# Peripherals.net
KiCad netlist of a schematic drawn in Altium Designer
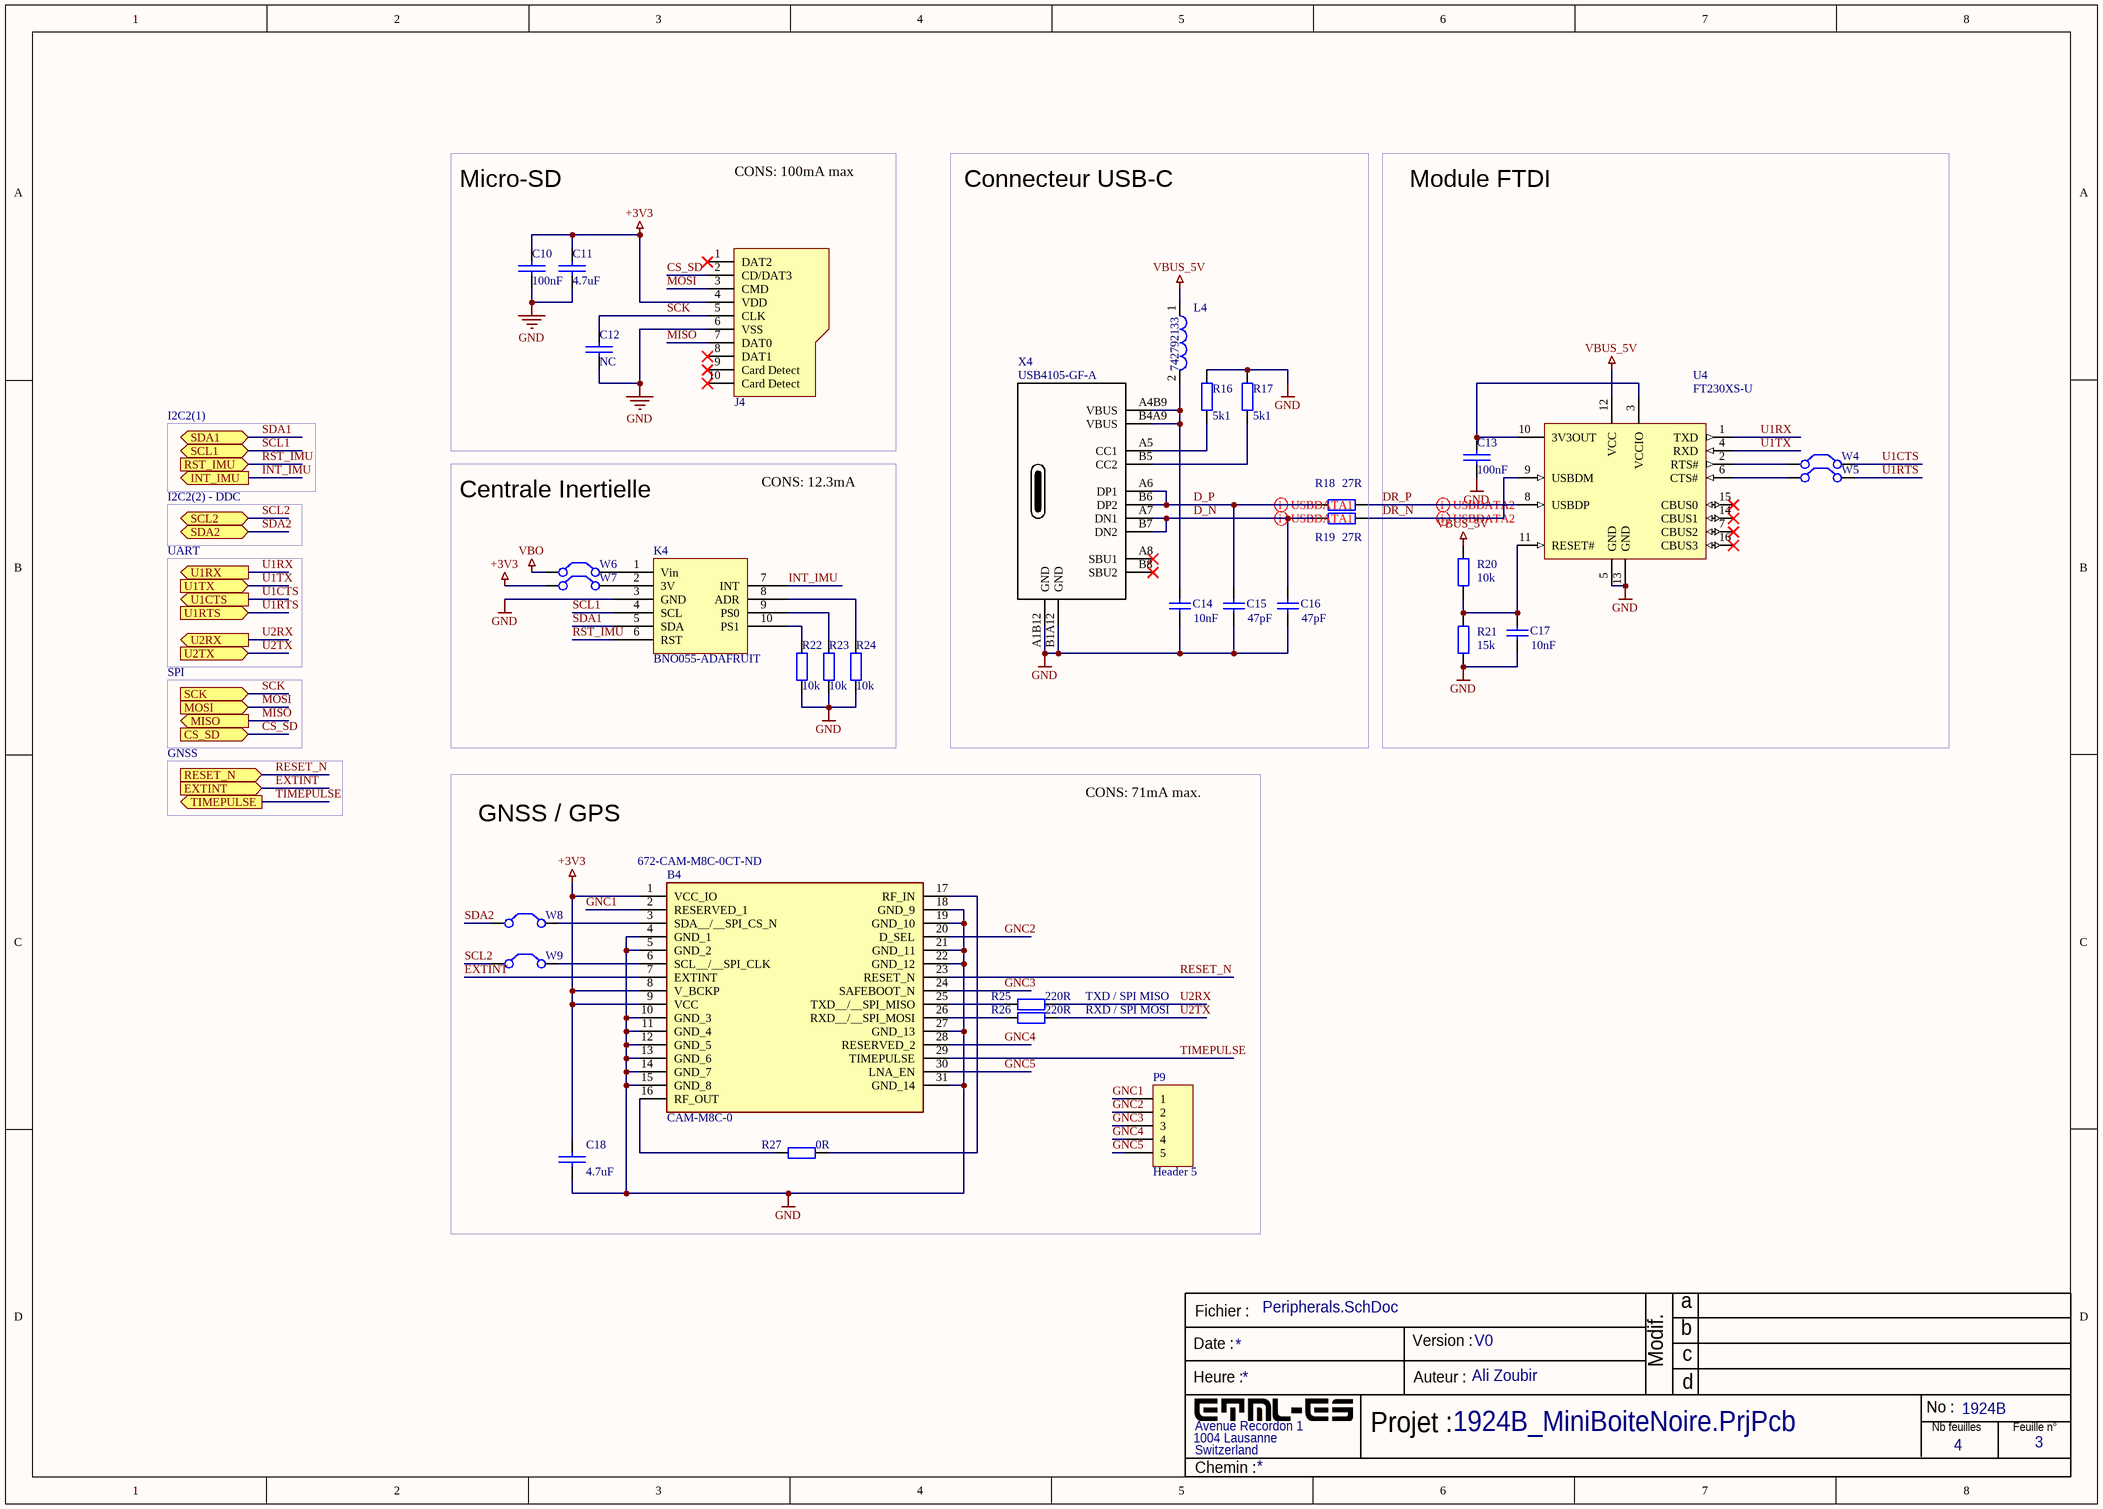
[diagram p0: Peripherals.SchDoc]

(export (version "E")
  (design (tool "Eeschema 10.0.6"))
  (components
    (comp (ref "B4")
      (value "CAM-M8C-0")
      (footprint "CAMM8C0")
      (description "RF RCVR GNSS/GPS 1.575GHZ MODULE")
      (fields
        (field (name "MOUSER PART NUMBER") "377-CAM-M8C-0")
        (field (name "SUPPLIER PART NUMBER 1") "672-CAM-M8C-0CT-ND")
      )
      (libsource (lib "CAM-M8C-0") (part "CAM-M8C-0"))
    )
    (comp (ref "C10") (value "100nF") (footprint "Cap_0805") (libsource (lib "*") (part "C")))
    (comp (ref "C11") (value "4.7uF") (footprint "Cap_0805") (libsource (lib "*") (part "C")))
    (comp (ref "C12") (value "NC") (footprint "Cap_0805") (libsource (lib "*") (part "C")))
    (comp (ref "C13") (value "100nF") (footprint "Cap_0805") (libsource (lib "*") (part "C")))
    (comp (ref "C14")
      (value "10nF")
      (footprint "6-0805_L")
      (description "Capacitor")
      (fields (field (name "PUBLISHER") "Altium Limited"))
      (libsource (lib "Miscellaneous Devices") (part "Cap"))
    )
    (comp (ref "C15")
      (value "47pF")
      (footprint "6-0805_L")
      (description "Capacitor")
      (fields (field (name "PUBLISHER") "Altium Limited"))
      (libsource (lib "Miscellaneous Devices") (part "Cap"))
    )
    (comp (ref "C16")
      (value "47pF")
      (footprint "6-0805_L")
      (description "Capacitor")
      (fields (field (name "PUBLISHER") "Altium Limited"))
      (libsource (lib "Miscellaneous Devices") (part "Cap"))
    )
    (comp (ref "C17")
      (value "10nF")
      (footprint "Cap_0805")
      (description "Capacitor")
      (fields (field (name "PUBLISHER") "Altium Limited"))
      (libsource (lib "Miscellaneous Devices") (part "Cap"))
    )
    (comp (ref "C18") (value "4.7uF") (footprint "Cap_0805") (libsource (lib "*") (part "C")))
    (comp (ref "J4")
      (value "693071010811")
      (footprint "uSD-WE-693071010811")
      (description "WR-CRD Micro SD Card Connector Push & Push")
      (fields (field (name "MANUFACTURER") "Wurth Elektronik"))
      (libsource (lib "AZR-LIB") (part "uSD-WE-693071010811"))
    )
    (comp (ref "K4")
      (value "BNO055-ADAFRUIT")
      (footprint "BNO055-ADAFRUIT_NO_HOLES")
      (libsource (lib "2221-LIB") (part "BNO055-ADAFRUIT"))
    )
    (comp (ref "L4")
      (value "742792133")
      (footprint "SMD-1206")
      (description "SMD EMI Suppression Ferrite Bead WE-CBF, Z = 600 Ohm")
      (libsource (lib "Altium Content Vault") (part "PAS-IND-INDUCTOR-2"))
    )
    (comp (ref "P9")
      (value "Header 5")
      (footprint "HDR1X5")
      (description "Header, 5-Pin")
      (fields (field (name "PUBLISHER") "Altium Limited"))
      (libsource (lib "Miscellaneous Connectors") (part "Header 5"))
    )
    (comp (ref "R16")
      (value "5k1")
      (footprint "RES_0805")
      (description "Res 0805")
      (fields (field (name "PUBLISHER") "Altium Limited"))
      (libsource (lib "Miscellaneous Devices") (part "Res2"))
    )
    (comp (ref "R17")
      (value "5k1")
      (footprint "RES_0805")
      (description "Res 0805")
      (fields (field (name "PUBLISHER") "Altium Limited"))
      (libsource (lib "Miscellaneous Devices") (part "Res2"))
    )
    (comp (ref "R18")
      (value "27R")
      (footprint "RES_0805")
      (description "Res 0805")
      (fields (field (name "PUBLISHER") "Altium Limited"))
      (libsource (lib "") (part "Res2_2"))
    )
    (comp (ref "R19")
      (value "27R")
      (footprint "RES_0805")
      (description "Res 0805")
      (fields (field (name "PUBLISHER") "Altium Limited"))
      (libsource (lib "") (part "Res2_2"))
    )
    (comp (ref "R20")
      (value "10k")
      (footprint "RES_0805")
      (description "Res 0805")
      (fields (field (name "PUBLISHER") "Altium Limited"))
      (libsource (lib "Miscellaneous Devices") (part "Res2"))
    )
    (comp (ref "R21")
      (value "15k")
      (footprint "RES_0805")
      (description "Res 0805")
      (fields (field (name "PUBLISHER") "Altium Limited"))
      (libsource (lib "Miscellaneous Devices") (part "Res2"))
    )
    (comp (ref "R22")
      (value "10k")
      (footprint "RES_0805")
      (description "Res 0805")
      (fields (field (name "PUBLISHER") "Altium Limited"))
      (libsource (lib "Miscellaneous Devices") (part "Res2"))
    )
    (comp (ref "R23")
      (value "10k")
      (footprint "RES_0805")
      (description "Res 0805")
      (fields (field (name "PUBLISHER") "Altium Limited"))
      (libsource (lib "Miscellaneous Devices") (part "Res2"))
    )
    (comp (ref "R24")
      (value "10k")
      (footprint "RES_0805")
      (description "Res 0805")
      (fields (field (name "PUBLISHER") "Altium Limited"))
      (libsource (lib "Miscellaneous Devices") (part "Res2"))
    )
    (comp (ref "R25")
      (value "220R")
      (footprint "RES_0805")
      (description "Res 0805")
      (fields (field (name "PUBLISHER") "Altium Limited"))
      (libsource (lib "") (part "Res2_1"))
    )
    (comp (ref "R26")
      (value "220R")
      (footprint "RES_0805")
      (description "Res 0805")
      (fields (field (name "PUBLISHER") "Altium Limited"))
      (libsource (lib "") (part "Res2_1"))
    )
    (comp (ref "R27")
      (value "0R")
      (footprint "RES_0805")
      (description "Res 0805")
      (fields (field (name "Comment") "220R") (field (name "PUBLISHER") "Altium Limited"))
      (libsource (lib "") (part "Res2_1"))
    )
    (comp (ref "U4")
      (value "FT230XS-U")
      (footprint "SSOP-16_N")
      (fields (field (name "MANUFACTURER") "FTDI"))
      (libsource (lib "Altium Content Vault") (part "COM-USB-FT230XS-IL16"))
    )
    (comp (ref "W4")
      (value "Jumper")
      (footprint "JUMPER")
      (description "Jumper Wire")
      (fields (field (name "PUBLISHER") "Altium Limited"))
      (libsource (lib "Miscellaneous Devices") (part "Jumper"))
    )
    (comp (ref "W5")
      (value "Jumper")
      (footprint "JUMPER")
      (description "Jumper Wire")
      (fields (field (name "PUBLISHER") "Altium Limited"))
      (libsource (lib "Miscellaneous Devices") (part "Jumper"))
    )
    (comp (ref "W6")
      (value "Jumper")
      (footprint "JUMPER")
      (description "Jumper Wire")
      (fields (field (name "PUBLISHER") "Altium Limited"))
      (libsource (lib "Miscellaneous Devices") (part "Jumper"))
    )
    (comp (ref "W7")
      (value "Jumper")
      (footprint "JUMPER")
      (description "Jumper Wire")
      (fields (field (name "PUBLISHER") "Altium Limited"))
      (libsource (lib "Miscellaneous Devices") (part "Jumper"))
    )
    (comp (ref "W8")
      (value "Jumper")
      (footprint "JUMPER")
      (description "Jumper Wire")
      (fields (field (name "PUBLISHER") "Altium Limited"))
      (libsource (lib "Miscellaneous Devices") (part "Jumper"))
    )
    (comp (ref "W9")
      (value "Jumper")
      (footprint "JUMPER")
      (description "Jumper Wire")
      (fields (field (name "PUBLISHER") "Altium Limited"))
      (libsource (lib "Miscellaneous Devices") (part "Jumper"))
    )
    (comp (ref "X4")
      (value "USB4105-GF-A")
      (footprint "GCT_USB4105-GF-A")
      (description "USB4105-GF-A USB connector")
      (libsource (lib "2221-LIB") (part "USB-C Type 2.0"))
    )
  )
  (nets
    (net (code "1") (name "+3V3") (class "Default")
      (node (ref "B4") (pin "1") (pinfunction "VCC_IO_1") (pintype "passive"))
      (node (ref "B4") (pin "8") (pinfunction "V_BCKP_8") (pintype "passive"))
      (node (ref "B4") (pin "9") (pinfunction "VCC_9") (pintype "passive"))
      (node (ref "C10") (pin "1") (pinfunction "1_1") (pintype "passive"))
      (node (ref "C11") (pin "1") (pinfunction "1_1") (pintype "passive"))
      (node (ref "C18") (pin "1") (pinfunction "1_1") (pintype "passive"))
      (node (ref "J4") (pin "4") (pinfunction "VDD_4") (pintype "passive"))
      (node (ref "W7") (pin "1") (pinfunction "C1_1") (pintype "passive"))
    )
    (net (code "2") (name "/CS_SD") (class "Default")
      (node (ref "J4") (pin "2") (pinfunction "CD/DAT3_2") (pintype "passive"))
    )
    (net (code "3") (name "/DR_N") (class "Default")
      (node (ref "R19") (pin "2") (pinfunction "2_2") (pintype "passive"))
      (node (ref "U4") (pin "9") (pinfunction "USBDM_9") (pintype "input"))
    )
    (net (code "4") (name "/DR_P") (class "Default")
      (node (ref "R18") (pin "2") (pinfunction "2_2") (pintype "passive"))
      (node (ref "U4") (pin "8") (pinfunction "USBDP_8") (pintype "input"))
    )
    (net (code "5") (name "/D_N") (class "Default")
      (node (ref "C16") (pin "2") (pinfunction "2_2") (pintype "passive"))
      (node (ref "R19") (pin "1") (pinfunction "1_1") (pintype "passive"))
      (node (ref "X4") (pin "A7") (pinfunction "DN1_A7") (pintype "passive"))
      (node (ref "X4") (pin "B7") (pinfunction "DN2_B7") (pintype "passive"))
    )
    (net (code "6") (name "/D_P") (class "Default")
      (node (ref "C15") (pin "2") (pinfunction "2_2") (pintype "passive"))
      (node (ref "R18") (pin "1") (pinfunction "1_1") (pintype "passive"))
      (node (ref "X4") (pin "A6") (pinfunction "DP1_A6") (pintype "passive"))
      (node (ref "X4") (pin "B6") (pinfunction "DP2_B6") (pintype "passive"))
    )
    (net (code "7") (name "/EXTINT") (class "Default")
      (node (ref "B4") (pin "7") (pinfunction "EXTINT_7") (pintype "passive"))
    )
    (net (code "8") (name "/GNC1") (class "Default")
      (node (ref "B4") (pin "2") (pinfunction "RESERVED_1_2") (pintype "passive"))
      (node (ref "P9") (pin "1") (pinfunction "1_1") (pintype "passive"))
    )
    (net (code "9") (name "/GNC2") (class "Default")
      (node (ref "B4") (pin "20") (pinfunction "D_SEL_20") (pintype "passive"))
      (node (ref "P9") (pin "2") (pinfunction "2_2") (pintype "passive"))
    )
    (net (code "10") (name "/GNC3") (class "Default")
      (node (ref "B4") (pin "24") (pinfunction "SAFEBOOT_N_24") (pintype "passive"))
      (node (ref "P9") (pin "3") (pinfunction "3_3") (pintype "passive"))
    )
    (net (code "11") (name "/GNC4") (class "Default")
      (node (ref "B4") (pin "28") (pinfunction "RESERVED_2_28") (pintype "passive"))
      (node (ref "P9") (pin "4") (pinfunction "4_4") (pintype "passive"))
    )
    (net (code "12") (name "/GNC5") (class "Default")
      (node (ref "B4") (pin "30") (pinfunction "LNA_EN_30") (pintype "passive"))
      (node (ref "P9") (pin "5") (pinfunction "5_5") (pintype "passive"))
    )
    (net (code "13") (name "/INT_IMU") (class "Default")
      (node (ref "K4") (pin "7") (pinfunction "INT_7") (pintype "passive"))
    )
    (net (code "14") (name "/MISO") (class "Default")
      (node (ref "J4") (pin "7") (pinfunction "DAT0_7") (pintype "passive"))
    )
    (net (code "15") (name "/MOSI") (class "Default")
      (node (ref "J4") (pin "3") (pinfunction "CMD_3") (pintype "passive"))
    )
    (net (code "16") (name "/RESET_N") (class "Default")
      (node (ref "B4") (pin "23") (pinfunction "RESET_N_23") (pintype "passive"))
    )
    (net (code "17") (name "/RST_IMU") (class "Default")
      (node (ref "K4") (pin "6") (pinfunction "RST_6") (pintype "passive"))
    )
    (net (code "18") (name "/SCK") (class "Default")
      (node (ref "C12") (pin "1") (pinfunction "1_1") (pintype "passive"))
      (node (ref "J4") (pin "5") (pinfunction "CLK_5") (pintype "passive"))
    )
    (net (code "19") (name "/SCL1") (class "Default")
      (node (ref "K4") (pin "4") (pinfunction "SCL_4") (pintype "passive"))
    )
    (net (code "20") (name "/SCL2") (class "Default")
      (node (ref "W9") (pin "1") (pinfunction "C1_1") (pintype "passive"))
    )
    (net (code "21") (name "/SDA1") (class "Default")
      (node (ref "K4") (pin "5") (pinfunction "SDA_5") (pintype "passive"))
    )
    (net (code "22") (name "/SDA2") (class "Default")
      (node (ref "W8") (pin "1") (pinfunction "C1_1") (pintype "passive"))
    )
    (net (code "23") (name "/TIMEPULSE") (class "Default")
      (node (ref "B4") (pin "29") (pinfunction "TIMEPULSE_29") (pintype "passive"))
    )
    (net (code "24") (name "/U1CTS") (class "Default")
      (node (ref "W4") (pin "2") (pinfunction "C2_2") (pintype "passive"))
    )
    (net (code "25") (name "/U1RTS") (class "Default")
      (node (ref "W5") (pin "2") (pinfunction "C2_2") (pintype "passive"))
    )
    (net (code "26") (name "/U1RX") (class "Default")
      (node (ref "U4") (pin "1") (pinfunction "TXD_1") (pintype "output"))
    )
    (net (code "27") (name "/U1TX") (class "Default")
      (node (ref "U4") (pin "4") (pinfunction "RXD_4") (pintype "input"))
    )
    (net (code "28") (name "/U2RX") (class "Default")
      (node (ref "R25") (pin "1") (pinfunction "1_1") (pintype "passive"))
    )
    (net (code "29") (name "/U2TX") (class "Default")
      (node (ref "R26") (pin "1") (pinfunction "1_1") (pintype "passive"))
    )
    (net (code "30") (name "GND") (class "Default")
      (node (ref "B4") (pin "10") (pinfunction "GND_3_10") (pintype "passive"))
      (node (ref "B4") (pin "11") (pinfunction "GND_4_11") (pintype "passive"))
      (node (ref "B4") (pin "12") (pinfunction "GND_5_12") (pintype "passive"))
      (node (ref "B4") (pin "13") (pinfunction "GND_6_13") (pintype "passive"))
      (node (ref "B4") (pin "14") (pinfunction "GND_7_14") (pintype "passive"))
      (node (ref "B4") (pin "15") (pinfunction "GND_8_15") (pintype "passive"))
      (node (ref "B4") (pin "18") (pinfunction "GND_9_18") (pintype "passive"))
      (node (ref "B4") (pin "19") (pinfunction "GND_10_19") (pintype "passive"))
      (node (ref "B4") (pin "21") (pinfunction "GND_11_21") (pintype "passive"))
      (node (ref "B4") (pin "22") (pinfunction "GND_12_22") (pintype "passive"))
      (node (ref "B4") (pin "27") (pinfunction "GND_13_27") (pintype "passive"))
      (node (ref "B4") (pin "31") (pinfunction "GND_14_31") (pintype "passive"))
      (node (ref "B4") (pin "4") (pinfunction "GND_1_4") (pintype "passive"))
      (node (ref "B4") (pin "5") (pinfunction "GND_2_5") (pintype "passive"))
      (node (ref "C10") (pin "2") (pinfunction "2_2") (pintype "passive"))
      (node (ref "C11") (pin "2") (pinfunction "2_2") (pintype "passive"))
      (node (ref "C12") (pin "2") (pinfunction "2_2") (pintype "passive"))
      (node (ref "C13") (pin "2") (pinfunction "2_2") (pintype "passive"))
      (node (ref "C14") (pin "1") (pinfunction "1_1") (pintype "passive"))
      (node (ref "C15") (pin "1") (pinfunction "1_1") (pintype "passive"))
      (node (ref "C16") (pin "1") (pinfunction "1_1") (pintype "passive"))
      (node (ref "C17") (pin "1") (pinfunction "1_1") (pintype "passive"))
      (node (ref "C18") (pin "2") (pinfunction "2_2") (pintype "passive"))
      (node (ref "J4") (pin "6") (pinfunction "VSS_6") (pintype "passive"))
      (node (ref "K4") (pin "3") (pinfunction "GND_3") (pintype "passive"))
      (node (ref "R16") (pin "2") (pinfunction "2_2") (pintype "passive"))
      (node (ref "R17") (pin "2") (pinfunction "2_2") (pintype "passive"))
      (node (ref "R21") (pin "1") (pinfunction "1_1") (pintype "passive"))
      (node (ref "R22") (pin "1") (pinfunction "1_1") (pintype "passive"))
      (node (ref "R23") (pin "1") (pinfunction "1_1") (pintype "passive"))
      (node (ref "R24") (pin "1") (pinfunction "1_1") (pintype "passive"))
      (node (ref "U4") (pin "13") (pinfunction "GND_13") (pintype "power_in"))
      (node (ref "U4") (pin "5") (pinfunction "GND_5") (pintype "power_in"))
      (node (ref "X4") (pin "A1B12") (pinfunction "GND_A1B12") (pintype "passive"))
      (node (ref "X4") (pin "B1A12") (pinfunction "GND_B1A12") (pintype "passive"))
    )
    (net (code "31") (name "Net-(B4-RF_IN)") (class "Default")
      (node (ref "B4") (pin "17") (pinfunction "RF_IN_17") (pintype "passive"))
      (node (ref "R27") (pin "1") (pinfunction "1_1") (pintype "passive"))
    )
    (net (code "32") (name "Net-(B4-RF_OUT)") (class "Default")
      (node (ref "B4") (pin "16") (pinfunction "RF_OUT_16") (pintype "passive"))
      (node (ref "R27") (pin "2") (pinfunction "2_2") (pintype "passive"))
    )
    (net (code "33") (name "Net-(B4-RXD__{slash}__SPI_MOSI)") (class "Default")
      (node (ref "B4") (pin "26") (pinfunction "RXD__/__SPI_MOSI_26") (pintype "passive"))
      (node (ref "R26") (pin "2") (pinfunction "2_2") (pintype "passive"))
    )
    (net (code "34") (name "Net-(B4-SCL__{slash}__SPI_CLK)") (class "Default")
      (node (ref "B4") (pin "6") (pinfunction "SCL__/__SPI_CLK_6") (pintype "passive"))
      (node (ref "W9") (pin "2") (pinfunction "C2_2") (pintype "passive"))
    )
    (net (code "35") (name "Net-(B4-SDA__{slash}__SPI_CS_N)") (class "Default")
      (node (ref "B4") (pin "3") (pinfunction "SDA__/__SPI_CS_N_3") (pintype "passive"))
      (node (ref "W8") (pin "2") (pinfunction "C2_2") (pintype "passive"))
    )
    (net (code "36") (name "Net-(B4-TXD__{slash}__SPI_MISO)") (class "Default")
      (node (ref "B4") (pin "25") (pinfunction "TXD__/__SPI_MISO_25") (pintype "passive"))
      (node (ref "R25") (pin "2") (pinfunction "2_2") (pintype "passive"))
    )
    (net (code "37") (name "Net-(C14-Pad2)") (class "Default")
      (node (ref "C14") (pin "2") (pinfunction "2_2") (pintype "passive"))
      (node (ref "L4") (pin "2") (pinfunction "2_2") (pintype "passive"))
      (node (ref "X4") (pin "A4B9") (pinfunction "VBUS_A4B9") (pintype "passive"))
      (node (ref "X4") (pin "B4A9") (pinfunction "VBUS_B4A9") (pintype "passive"))
    )
    (net (code "38") (name "Net-(K4-3V)") (class "Default")
      (node (ref "K4") (pin "2") (pinfunction "3V_2") (pintype "passive"))
      (node (ref "W7") (pin "2") (pinfunction "C2_2") (pintype "passive"))
    )
    (net (code "39") (name "Net-(K4-ADR)") (class "Default")
      (node (ref "K4") (pin "8") (pinfunction "ADR_8") (pintype "passive"))
      (node (ref "R24") (pin "2") (pinfunction "2_2") (pintype "passive"))
    )
    (net (code "40") (name "Net-(K4-PS0)") (class "Default")
      (node (ref "K4") (pin "9") (pinfunction "PS0_9") (pintype "passive"))
      (node (ref "R23") (pin "2") (pinfunction "2_2") (pintype "passive"))
    )
    (net (code "41") (name "Net-(K4-PS1)") (class "Default")
      (node (ref "K4") (pin "10") (pinfunction "PS1_10") (pintype "passive"))
      (node (ref "R22") (pin "2") (pinfunction "2_2") (pintype "passive"))
    )
    (net (code "42") (name "Net-(K4-Vin)") (class "Default")
      (node (ref "K4") (pin "1") (pinfunction "Vin_1") (pintype "passive"))
      (node (ref "W6") (pin "2") (pinfunction "C2_2") (pintype "passive"))
    )
    (net (code "43") (name "Net-(U4-3V3OUT)") (class "Default")
      (node (ref "C13") (pin "1") (pinfunction "1_1") (pintype "passive"))
      (node (ref "U4") (pin "10") (pinfunction "3V3OUT_10") (pintype "power_in"))
      (node (ref "U4") (pin "3") (pinfunction "VCCIO_3") (pintype "power_in"))
    )
    (net (code "44") (name "Net-(U4-CTS#)") (class "Default")
      (node (ref "U4") (pin "6") (pinfunction "CTS#_6") (pintype "input"))
      (node (ref "W5") (pin "1") (pinfunction "C1_1") (pintype "passive"))
    )
    (net (code "45") (name "Net-(U4-RESET#)") (class "Default")
      (node (ref "C17") (pin "2") (pinfunction "2_2") (pintype "passive"))
      (node (ref "R20") (pin "1") (pinfunction "1_1") (pintype "passive"))
      (node (ref "R21") (pin "2") (pinfunction "2_2") (pintype "passive"))
      (node (ref "U4") (pin "11") (pinfunction "RESET#_11") (pintype "input"))
    )
    (net (code "46") (name "Net-(U4-RTS#)") (class "Default")
      (node (ref "U4") (pin "2") (pinfunction "RTS#_2") (pintype "output"))
      (node (ref "W4") (pin "1") (pinfunction "C1_1") (pintype "passive"))
    )
    (net (code "47") (name "Net-(X4-CC1)") (class "Default")
      (node (ref "R16") (pin "1") (pinfunction "1_1") (pintype "passive"))
      (node (ref "X4") (pin "A5") (pinfunction "CC1_A5") (pintype "passive"))
    )
    (net (code "48") (name "Net-(X4-CC2)") (class "Default")
      (node (ref "R17") (pin "1") (pinfunction "1_1") (pintype "passive"))
      (node (ref "X4") (pin "B5") (pinfunction "CC2_B5") (pintype "passive"))
    )
    (net (code "49") (name "VBO") (class "Default")
      (node (ref "W6") (pin "1") (pinfunction "C1_1") (pintype "passive"))
    )
    (net (code "50") (name "VBUS_5V") (class "Default")
      (node (ref "L4") (pin "1") (pinfunction "1_1") (pintype "passive"))
      (node (ref "R20") (pin "2") (pinfunction "2_2") (pintype "passive"))
      (node (ref "U4") (pin "12") (pinfunction "VCC_12") (pintype "power_in"))
    )
    (net (code "51") (name "unconnected-(J4-Card_Detect-Pad9)") (class "Default")
      (node (ref "J4") (pin "9") (pinfunction "Card_Detect_9") (pintype "passive+no_connect"))
    )
    (net (code "52") (name "unconnected-(J4-Card_Detect-Pad10)") (class "Default")
      (node (ref "J4") (pin "10") (pinfunction "Card_Detect_10") (pintype "passive+no_connect"))
    )
    (net (code "53") (name "unconnected-(J4-DAT1-Pad8)") (class "Default")
      (node (ref "J4") (pin "8") (pinfunction "DAT1_8") (pintype "passive+no_connect"))
    )
    (net (code "54") (name "unconnected-(J4-DAT2-Pad1)") (class "Default")
      (node (ref "J4") (pin "1") (pinfunction "DAT2_1") (pintype "passive+no_connect"))
    )
    (net (code "55") (name "unconnected-(U4-CBUS0-Pad15)") (class "Default")
      (node (ref "U4") (pin "15") (pinfunction "CBUS0_15") (pintype "bidirectional+no_connect"))
    )
    (net (code "56") (name "unconnected-(U4-CBUS1-Pad14)") (class "Default")
      (node (ref "U4") (pin "14") (pinfunction "CBUS1_14") (pintype "bidirectional+no_connect"))
    )
    (net (code "57") (name "unconnected-(U4-CBUS2-Pad7)") (class "Default")
      (node (ref "U4") (pin "7") (pinfunction "CBUS2_7") (pintype "bidirectional+no_connect"))
    )
    (net (code "58") (name "unconnected-(U4-CBUS3-Pad16)") (class "Default")
      (node (ref "U4") (pin "16") (pinfunction "CBUS3_16") (pintype "bidirectional+no_connect"))
    )
    (net (code "59") (name "unconnected-(X4-SBU1-PadA8)") (class "Default")
      (node (ref "X4") (pin "A8") (pinfunction "SBU1_A8") (pintype "passive+no_connect"))
    )
    (net (code "60") (name "unconnected-(X4-SBU2-PadB8)") (class "Default")
      (node (ref "X4") (pin "B8") (pinfunction "SBU2_B8") (pintype "passive+no_connect"))
    )
  )
)
